# embededwebcam.net
KiCad netlist of a schematic drawn in EAGLE
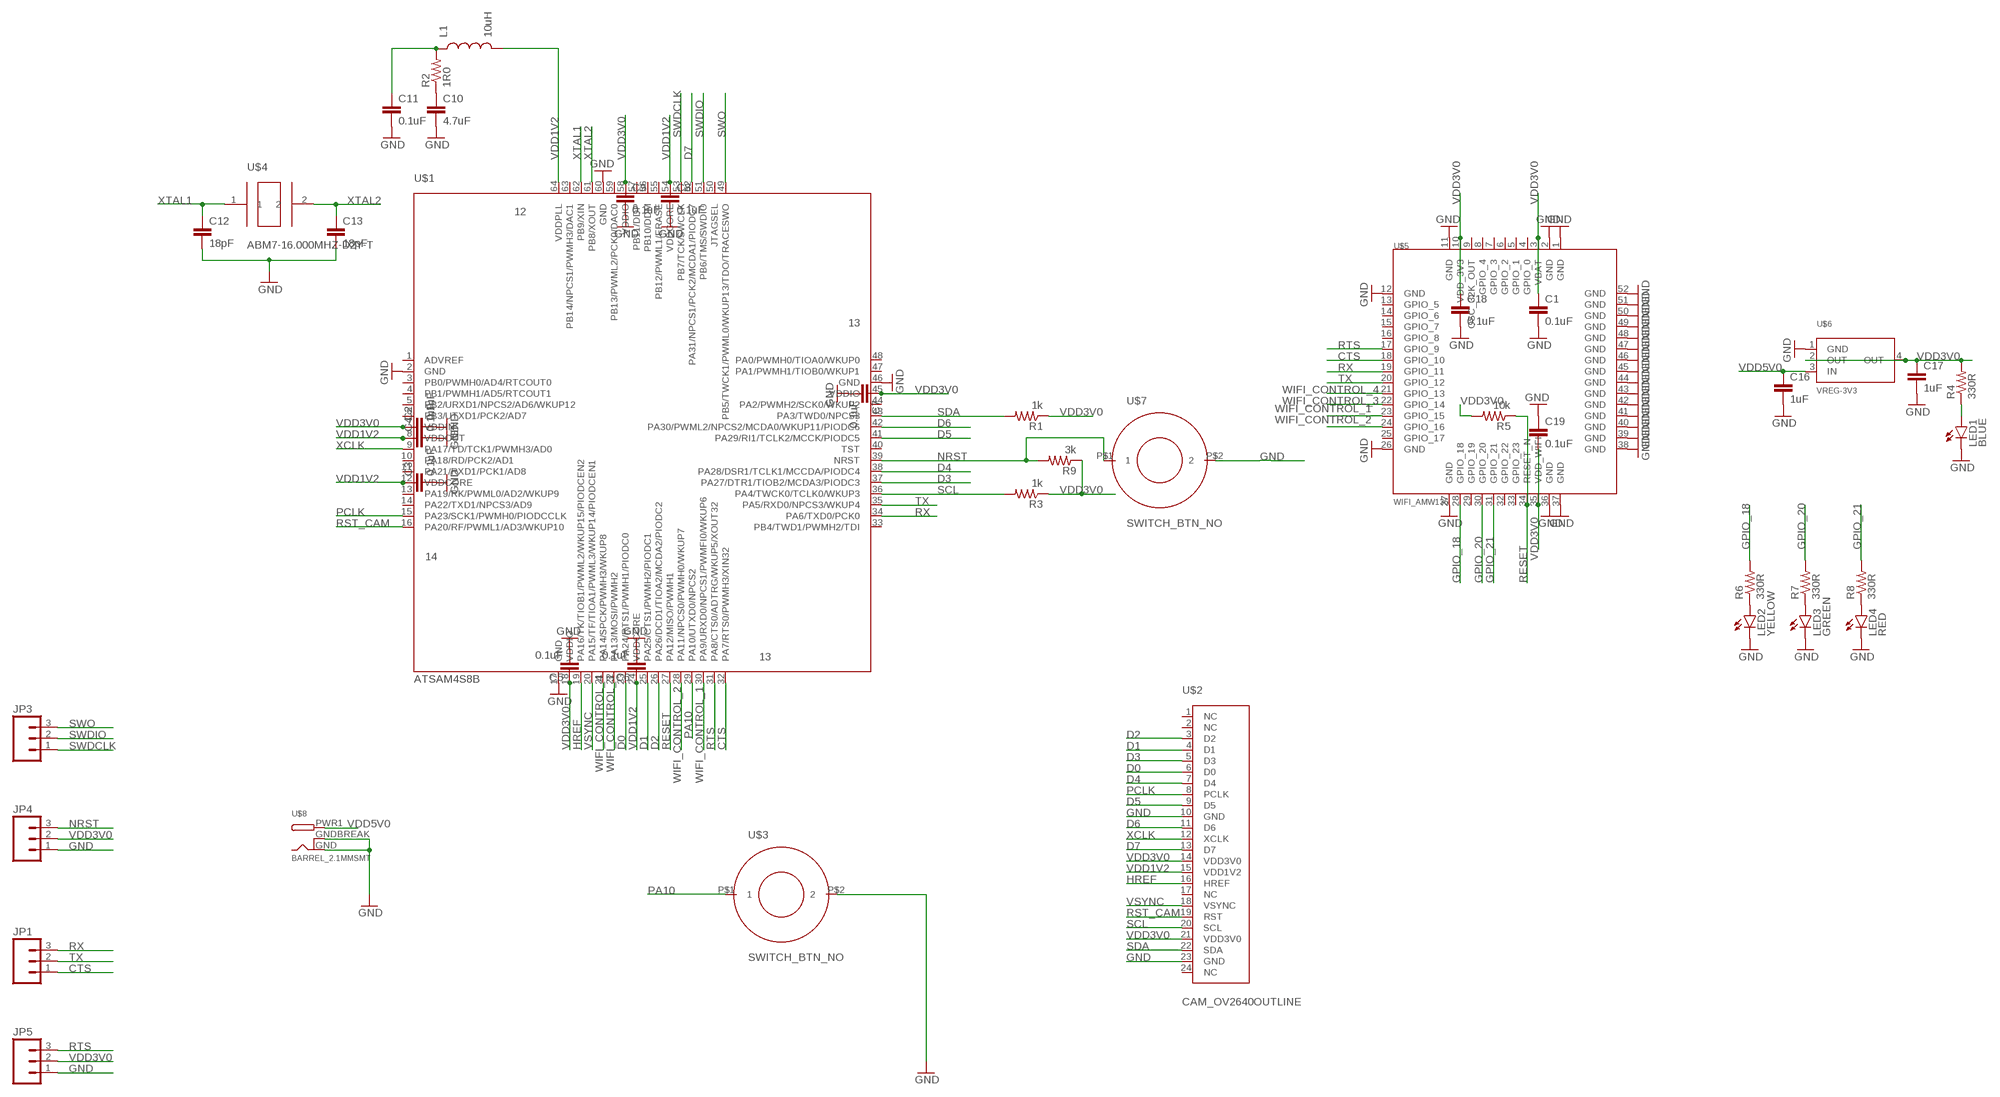
[diagram p0: schematic, sheet 1]

(export (version "E")
  (design (tool "Eeschema 10.0.6"))
  (components
    (comp (ref "C1")
      (value "0.1uF")
      (footprint "eagle-import:0805")
      (libsource (lib "eagle-import") (part "CAP"))
    )
    (comp (ref "C2")
      (value "0.1uF")
      (footprint "eagle-import:0805")
      (libsource (lib "eagle-import") (part "CAP0805"))
    )
    (comp (ref "C3")
      (value "0.1uF")
      (footprint "eagle-import:0805")
      (libsource (lib "eagle-import") (part "CAP0805"))
    )
    (comp (ref "C4")
      (value "0.1uF")
      (footprint "eagle-import:0805")
      (libsource (lib "eagle-import") (part "CAP0805"))
    )
    (comp (ref "C5")
      (value "0.1uF")
      (footprint "eagle-import:0805")
      (libsource (lib "eagle-import") (part "CAP0805"))
    )
    (comp (ref "C6")
      (value "0.1uF")
      (footprint "eagle-import:0805")
      (libsource (lib "eagle-import") (part "CAP0805"))
    )
    (comp (ref "C7")
      (value "0.1uF")
      (footprint "eagle-import:0805")
      (libsource (lib "eagle-import") (part "CAP0805"))
    )
    (comp (ref "C8")
      (value "0.1uF")
      (footprint "eagle-import:0805")
      (libsource (lib "eagle-import") (part "CAP0805"))
    )
    (comp (ref "C9")
      (value "0.1uF")
      (footprint "eagle-import:0805")
      (libsource (lib "eagle-import") (part "CAP0805"))
    )
    (comp (ref "C10")
      (value "4.7uF")
      (footprint "eagle-import:0805")
      (libsource (lib "eagle-import") (part "CAP0805"))
    )
    (comp (ref "C11")
      (value "0.1uF")
      (footprint "eagle-import:0805")
      (libsource (lib "eagle-import") (part "CAP0805"))
    )
    (comp (ref "C12")
      (value "18pF")
      (footprint "eagle-import:0805")
      (libsource (lib "eagle-import") (part "CAP0805"))
    )
    (comp (ref "C13")
      (value "18pF")
      (footprint "eagle-import:0805")
      (libsource (lib "eagle-import") (part "CAP0805"))
    )
    (comp (ref "C16")
      (value "1uF")
      (footprint "eagle-import:0805")
      (libsource (lib "eagle-import") (part "CAP"))
    )
    (comp (ref "C17")
      (value "1uF")
      (footprint "eagle-import:0805")
      (libsource (lib "eagle-import") (part "CAP"))
    )
    (comp (ref "C18")
      (value "0.1uF")
      (footprint "eagle-import:0805")
      (libsource (lib "eagle-import") (part "CAP"))
    )
    (comp (ref "C19")
      (value "0.1uF")
      (footprint "eagle-import:0805")
      (libsource (lib "eagle-import") (part "CAP"))
    )
    (comp (ref "JP1")
      (value "M03PTH")
      (footprint "eagle-import:1X03")
      (libsource (lib "eagle-import") (part "M03PTH"))
    )
    (comp (ref "JP3")
      (value "M03PTH")
      (footprint "eagle-import:1X03")
      (libsource (lib "eagle-import") (part "M03PTH"))
    )
    (comp (ref "JP4")
      (value "M03PTH")
      (footprint "eagle-import:1X03")
      (libsource (lib "eagle-import") (part "M03PTH"))
    )
    (comp (ref "JP5")
      (value "M03PTH")
      (footprint "eagle-import:1X03")
      (libsource (lib "eagle-import") (part "M03PTH"))
    )
    (comp (ref "L1")
      (value "10uH")
      (footprint "eagle-import:0805")
      (libsource (lib "eagle-import") (part "INDUCTOR0805"))
    )
    (comp (ref "LED1")
      (value "BLUE")
      (footprint "eagle-import:LED-0603")
      (libsource (lib "eagle-import") (part "LED0603"))
    )
    (comp (ref "LED2")
      (value "YELLOW")
      (footprint "eagle-import:LED-0603")
      (libsource (lib "eagle-import") (part "LED0603"))
    )
    (comp (ref "LED3")
      (value "GREEN")
      (footprint "eagle-import:LED-0603")
      (libsource (lib "eagle-import") (part "LED0603"))
    )
    (comp (ref "LED4")
      (value "RED")
      (footprint "eagle-import:LED-0603")
      (libsource (lib "eagle-import") (part "LED0603"))
    )
    (comp (ref "R1")
      (value "1k")
      (footprint "eagle-import:0805")
      (libsource (lib "eagle-import") (part "RESISTOR0805-RES"))
    )
    (comp (ref "R2")
      (value "1R0")
      (footprint "eagle-import:0805")
      (libsource (lib "eagle-import") (part "RESISTOR0805-RES"))
    )
    (comp (ref "R3")
      (value "1k")
      (footprint "eagle-import:0805")
      (libsource (lib "eagle-import") (part "RESISTOR0805-RES"))
    )
    (comp (ref "R4")
      (value "330R")
      (footprint "eagle-import:0805")
      (libsource (lib "eagle-import") (part "RES"))
    )
    (comp (ref "R5")
      (value "10k")
      (footprint "eagle-import:0805")
      (libsource (lib "eagle-import") (part "RES"))
    )
    (comp (ref "R6")
      (value "330R")
      (footprint "eagle-import:0805")
      (libsource (lib "eagle-import") (part "RES"))
    )
    (comp (ref "R7")
      (value "330R")
      (footprint "eagle-import:0805")
      (libsource (lib "eagle-import") (part "RES"))
    )
    (comp (ref "R8")
      (value "330R")
      (footprint "eagle-import:0805")
      (libsource (lib "eagle-import") (part "RES"))
    )
    (comp (ref "R9")
      (value "3k")
      (footprint "eagle-import:0805")
      (libsource (lib "eagle-import") (part "RESISTOR0805-RES"))
    )
    (comp (ref "U$1")
      (value "ATSAM4S8B")
      (footprint "eagle-import:QFP50P1200X1200X160-64N")
      (libsource (lib "eagle-import") (part "ATSAM4S8B"))
    )
    (comp (ref "U$2")
      (value "CAM_OV2640OUTLINE")
      (footprint "eagle-import:CAM_CONN")
      (libsource (lib "eagle-import") (part "CAM_OV2640OUTLINE"))
    )
    (comp (ref "U$3")
      (value "SWITCH_BTN_NO")
      (footprint "eagle-import:BTN_2")
      (libsource (lib "eagle-import") (part "SWITCH_BTN_NO"))
    )
    (comp (ref "U$4")
      (value "ABM7-16.000MHZ-D2Y-T")
      (footprint "eagle-import:ABM7-16.000MHZ-D2Y-T")
      (libsource (lib "eagle-import") (part "ABM7-16.000MHZ-D2Y-T"))
    )
    (comp (ref "U$5")
      (value "WIFI_AMW136")
      (footprint "eagle-import:AMW136")
      (libsource (lib "eagle-import") (part "WIFI_AMW136"))
    )
    (comp (ref "U$6")
      (value "VREG-3V3")
      (footprint "eagle-import:R-PDSO-G4_TI")
      (libsource (lib "eagle-import") (part "VREG-3V3"))
    )
    (comp (ref "U$7")
      (value "SWITCH_BTN_NO")
      (footprint "eagle-import:BTN_2")
      (libsource (lib "eagle-import") (part "SWITCH_BTN_NO"))
    )
    (comp (ref "U$8")
      (value "BARREL_2.1MMSMT")
      (footprint "eagle-import:DCJACK_2MM_SMT")
      (libsource (lib "eagle-import") (part "BARREL_2.1MMSMT"))
    )
  )
  (nets
    (net (code "1") (name "/CTS") (class "Default")
      (node (ref "JP1") (pin "1") (pinfunction "1_1") (pintype "passive"))
      (node (ref "U$1") (pin "32") (pinfunction "PA7/RTS0/PWMH3/XIN32_32") (pintype "bidirectional"))
      (node (ref "U$5") (pin "18") (pinfunction "GPIO_10_18") (pintype "bidirectional"))
    )
    (net (code "2") (name "/D0") (class "Default")
      (node (ref "U$1") (pin "23") (pinfunction "PA24/RTS1/PWMH1/PIODC0_23") (pintype "bidirectional"))
      (node (ref "U$2") (pin "6") (pinfunction "D0_6") (pintype "bidirectional"))
    )
    (net (code "3") (name "/D1") (class "Default")
      (node (ref "U$1") (pin "25") (pinfunction "PA25/CTS1/PWMH2/PIODC1_25") (pintype "bidirectional"))
      (node (ref "U$2") (pin "4") (pinfunction "D1_4") (pintype "bidirectional"))
    )
    (net (code "4") (name "/D2") (class "Default")
      (node (ref "U$1") (pin "26") (pinfunction "PA26/DCD1/TIOA2/MCDA2/PIODC2_26") (pintype "bidirectional"))
      (node (ref "U$2") (pin "3") (pinfunction "D2_3") (pintype "bidirectional"))
    )
    (net (code "5") (name "/D3") (class "Default")
      (node (ref "U$1") (pin "37") (pinfunction "PA27/DTR1/TIOB2/MCDA3/PIODC3_37") (pintype "bidirectional"))
      (node (ref "U$2") (pin "5") (pinfunction "D3_5") (pintype "bidirectional"))
    )
    (net (code "6") (name "/D4") (class "Default")
      (node (ref "U$1") (pin "38") (pinfunction "PA28/DSR1/TCLK1/MCCDA/PIODC4_38") (pintype "bidirectional"))
      (node (ref "U$2") (pin "7") (pinfunction "D4_7") (pintype "bidirectional"))
    )
    (net (code "7") (name "/D5") (class "Default")
      (node (ref "U$1") (pin "41") (pinfunction "PA29/RI1/TCLK2/MCCK/PIODC5_41") (pintype "bidirectional"))
      (node (ref "U$2") (pin "9") (pinfunction "D5_9") (pintype "bidirectional"))
    )
    (net (code "8") (name "/D6") (class "Default")
      (node (ref "U$1") (pin "42") (pinfunction "PA30/PWML2/NPCS2/MCDA0/WKUP11/PIODC6_42") (pintype "bidirectional"))
      (node (ref "U$2") (pin "11") (pinfunction "D6_11") (pintype "bidirectional"))
    )
    (net (code "9") (name "/D7") (class "Default")
      (node (ref "U$1") (pin "52") (pinfunction "PA31/NPCS1/PCK2/MCDA1/PIODC7_52") (pintype "bidirectional"))
      (node (ref "U$2") (pin "13") (pinfunction "D7_13") (pintype "bidirectional"))
    )
    (net (code "10") (name "/GPIO_18") (class "Default")
      (node (ref "R6") (pin "2") (pinfunction "2_2") (pintype "passive"))
      (node (ref "U$5") (pin "28") (pinfunction "GPIO_18_28") (pintype "bidirectional"))
    )
    (net (code "11") (name "/GPIO_20") (class "Default")
      (node (ref "R7") (pin "2") (pinfunction "2_2") (pintype "passive"))
      (node (ref "U$5") (pin "30") (pinfunction "GPIO_20_30") (pintype "bidirectional"))
    )
    (net (code "12") (name "/GPIO_21") (class "Default")
      (node (ref "R8") (pin "2") (pinfunction "2_2") (pintype "passive"))
      (node (ref "U$5") (pin "31") (pinfunction "GPIO_21_31") (pintype "bidirectional"))
    )
    (net (code "13") (name "/HREF") (class "Default")
      (node (ref "U$1") (pin "19") (pinfunction "PA16/TK/TIOB1/PWML2/WKUP15/PIODCEN2_19") (pintype "bidirectional"))
      (node (ref "U$2") (pin "16") (pinfunction "HREF_16") (pintype "bidirectional"))
    )
    (net (code "14") (name "/NRST") (class "Default")
      (node (ref "JP4") (pin "3") (pinfunction "3_3") (pintype "passive"))
      (node (ref "R9") (pin "2") (pinfunction "2_2") (pintype "passive"))
      (node (ref "U$1") (pin "39") (pinfunction "NRST_39") (pintype "bidirectional"))
      (node (ref "U$7") (pin "P$1") (pinfunction "1_P$1") (pintype "bidirectional"))
    )
    (net (code "15") (name "/PA10") (class "Default")
      (node (ref "U$1") (pin "29") (pinfunction "PA10/UTXD0/NPCS2_29") (pintype "bidirectional"))
      (node (ref "U$3") (pin "P$1") (pinfunction "1_P$1") (pintype "bidirectional"))
    )
    (net (code "16") (name "/PCLK") (class "Default")
      (node (ref "U$1") (pin "15") (pinfunction "PA23/SCK1/PWMH0/PIODCCLK_15") (pintype "bidirectional"))
      (node (ref "U$2") (pin "8") (pinfunction "PCLK_8") (pintype "bidirectional"))
    )
    (net (code "17") (name "/RESET") (class "Default")
      (node (ref "R5") (pin "1") (pinfunction "1_1") (pintype "passive"))
      (node (ref "U$1") (pin "27") (pinfunction "PA12/MISO/PWMH1_27") (pintype "bidirectional"))
      (node (ref "U$5") (pin "34") (pinfunction "RESET_N_34") (pintype "bidirectional"))
    )
    (net (code "18") (name "/RST_CAM") (class "Default")
      (node (ref "U$1") (pin "16") (pinfunction "PA20/RF/PWML1/AD3/WKUP10_16") (pintype "bidirectional"))
      (node (ref "U$2") (pin "19") (pinfunction "RST_19") (pintype "bidirectional"))
    )
    (net (code "19") (name "/RTS") (class "Default")
      (node (ref "JP5") (pin "3") (pinfunction "3_3") (pintype "passive"))
      (node (ref "U$1") (pin "31") (pinfunction "PA8/CTS0/ADTRG/WKUP5/XOUT32_31") (pintype "bidirectional"))
      (node (ref "U$5") (pin "17") (pinfunction "GPIO_9_17") (pintype "bidirectional"))
    )
    (net (code "20") (name "/RX") (class "Default")
      (node (ref "JP1") (pin "3") (pinfunction "3_3") (pintype "passive"))
      (node (ref "U$1") (pin "34") (pinfunction "PA6/TXD0/PCK0_34") (pintype "bidirectional"))
      (node (ref "U$5") (pin "19") (pinfunction "GPIO_11_19") (pintype "bidirectional"))
    )
    (net (code "21") (name "/SCL") (class "Default")
      (node (ref "R3") (pin "2") (pinfunction "2_2") (pintype "passive"))
      (node (ref "U$1") (pin "36") (pinfunction "PA4/TWCK0/TCLK0/WKUP3_36") (pintype "bidirectional"))
      (node (ref "U$2") (pin "20") (pinfunction "SCL_20") (pintype "bidirectional"))
    )
    (net (code "22") (name "/SDA") (class "Default")
      (node (ref "R1") (pin "2") (pinfunction "2_2") (pintype "passive"))
      (node (ref "U$1") (pin "43") (pinfunction "PA3/TWD0/NPCS3_43") (pintype "bidirectional"))
      (node (ref "U$2") (pin "22") (pinfunction "SDA_22") (pintype "bidirectional"))
    )
    (net (code "23") (name "/SWDCLK") (class "Default")
      (node (ref "JP3") (pin "1") (pinfunction "1_1") (pintype "passive"))
      (node (ref "U$1") (pin "53") (pinfunction "PB7/TCK/SWCLK_53") (pintype "bidirectional"))
    )
    (net (code "24") (name "/SWDIO") (class "Default")
      (node (ref "JP3") (pin "2") (pinfunction "2_2") (pintype "passive"))
      (node (ref "U$1") (pin "51") (pinfunction "PB6/TMS/SWDIO_51") (pintype "bidirectional"))
    )
    (net (code "25") (name "/SWO") (class "Default")
      (node (ref "JP3") (pin "3") (pinfunction "3_3") (pintype "passive"))
      (node (ref "U$1") (pin "49") (pinfunction "PB5/TWCK1/PWML0/WKUP13/TDO/TRACESWO_49") (pintype "bidirectional"))
    )
    (net (code "26") (name "/TX") (class "Default")
      (node (ref "JP1") (pin "2") (pinfunction "2_2") (pintype "passive"))
      (node (ref "U$1") (pin "35") (pinfunction "PA5/RXD0/NPCS3/WKUP4_35") (pintype "bidirectional"))
      (node (ref "U$5") (pin "20") (pinfunction "GPIO_12_20") (pintype "bidirectional"))
    )
    (net (code "27") (name "/VDD1V2") (class "Default")
      (node (ref "C3") (pin "1") (pinfunction "1_1") (pintype "passive"))
      (node (ref "C4") (pin "1") (pinfunction "1_1") (pintype "passive"))
      (node (ref "C6") (pin "1") (pinfunction "1_1") (pintype "passive"))
      (node (ref "C8") (pin "1") (pinfunction "1_1") (pintype "passive"))
      (node (ref "L1") (pin "2") (pinfunction "2_2") (pintype "passive"))
      (node (ref "U$1") (pin "12") (pinfunction "VDDCORE_12") (pintype "bidirectional"))
      (node (ref "U$1") (pin "24") (pinfunction "VDDCORE_24") (pintype "bidirectional"))
      (node (ref "U$1") (pin "54") (pinfunction "VDDCORE_54") (pintype "bidirectional"))
      (node (ref "U$1") (pin "64") (pinfunction "VDDPLL_64") (pintype "bidirectional"))
      (node (ref "U$1") (pin "8") (pinfunction "VDDOUT_8") (pintype "bidirectional"))
      (node (ref "U$2") (pin "15") (pinfunction "VDD1V2_15") (pintype "bidirectional"))
    )
    (net (code "28") (name "/VDD3V0") (class "Default")
      (node (ref "C1") (pin "1") (pinfunction "1_1") (pintype "passive"))
      (node (ref "C17") (pin "1") (pinfunction "1_1") (pintype "passive"))
      (node (ref "C18") (pin "1") (pinfunction "1_1") (pintype "passive"))
      (node (ref "C19") (pin "2") (pinfunction "2_2") (pintype "passive"))
      (node (ref "C2") (pin "1") (pinfunction "1_1") (pintype "passive"))
      (node (ref "C5") (pin "1") (pinfunction "1_1") (pintype "passive"))
      (node (ref "C7") (pin "1") (pinfunction "1_1") (pintype "passive"))
      (node (ref "C9") (pin "1") (pinfunction "1_1") (pintype "passive"))
      (node (ref "JP4") (pin "2") (pinfunction "2_2") (pintype "passive"))
      (node (ref "JP5") (pin "2") (pinfunction "2_2") (pintype "passive"))
      (node (ref "R1") (pin "1") (pinfunction "1_1") (pintype "passive"))
      (node (ref "R3") (pin "1") (pinfunction "1_1") (pintype "passive"))
      (node (ref "R4") (pin "2") (pinfunction "2_2") (pintype "passive"))
      (node (ref "R5") (pin "2") (pinfunction "2_2") (pintype "passive"))
      (node (ref "R9") (pin "1") (pinfunction "1_1") (pintype "passive"))
      (node (ref "U$1") (pin "18") (pinfunction "VDDIO_18") (pintype "bidirectional"))
      (node (ref "U$1") (pin "45") (pinfunction "VDDIO_45") (pintype "bidirectional"))
      (node (ref "U$1") (pin "58") (pinfunction "VDDIO_58") (pintype "bidirectional"))
      (node (ref "U$1") (pin "7") (pinfunction "VDDIN_7") (pintype "bidirectional"))
      (node (ref "U$2") (pin "14") (pinfunction "VDD3V0_14") (pintype "bidirectional"))
      (node (ref "U$2") (pin "21") (pinfunction "VDD3V0_21") (pintype "bidirectional"))
      (node (ref "U$5") (pin "10") (pinfunction "VDD_3V3_10") (pintype "bidirectional"))
      (node (ref "U$5") (pin "3") (pinfunction "VBAT_3") (pintype "bidirectional"))
      (node (ref "U$5") (pin "35") (pinfunction "VDD_WIFI_35") (pintype "bidirectional"))
      (node (ref "U$6") (pin "2") (pinfunction "OUT_2") (pintype "bidirectional"))
      (node (ref "U$6") (pin "4") (pinfunction "OUT_4") (pintype "bidirectional"))
    )
    (net (code "29") (name "/VDD5V0") (class "Default")
      (node (ref "C16") (pin "1") (pinfunction "1_1") (pintype "passive"))
      (node (ref "U$6") (pin "3") (pinfunction "IN_3") (pintype "bidirectional"))
      (node (ref "U$8") (pin "PWR1") (pinfunction "PWR_PWR1") (pintype "power_in"))
    )
    (net (code "30") (name "/VSYNC") (class "Default")
      (node (ref "U$1") (pin "20") (pinfunction "PA15/TF/TIOA1/PWML3/WKUP14/PIODCEN1_20") (pintype "bidirectional"))
      (node (ref "U$2") (pin "18") (pinfunction "VSYNC_18") (pintype "bidirectional"))
    )
    (net (code "31") (name "/WIFI_CONTROL_1") (class "Default")
      (node (ref "U$1") (pin "30") (pinfunction "PA9/URXD0/NPCS1/PWMFI0/WKUP6_30") (pintype "bidirectional"))
      (node (ref "U$5") (pin "24") (pinfunction "GPIO_16_24") (pintype "bidirectional"))
    )
    (net (code "32") (name "/WIFI_CONTROL_2") (class "Default")
      (node (ref "U$1") (pin "28") (pinfunction "PA11/NPCS0/PWMH0/WKUP7_28") (pintype "bidirectional"))
      (node (ref "U$5") (pin "23") (pinfunction "GPIO_15_23") (pintype "bidirectional"))
    )
    (net (code "33") (name "/WIFI_CONTROL_3") (class "Default")
      (node (ref "U$1") (pin "22") (pinfunction "PA13/MOSI/PWMH2_22") (pintype "bidirectional"))
      (node (ref "U$5") (pin "22") (pinfunction "GPIO_14_22") (pintype "bidirectional"))
    )
    (net (code "34") (name "/WIFI_CONTROL_4") (class "Default")
      (node (ref "U$1") (pin "21") (pinfunction "PA14/SPCK/PWMH3/WKUP8_21") (pintype "bidirectional"))
      (node (ref "U$5") (pin "21") (pinfunction "GPIO_13_21") (pintype "bidirectional"))
    )
    (net (code "35") (name "/XCLK") (class "Default")
      (node (ref "U$1") (pin "9") (pinfunction "PA17/TD/TCK1/PWMH3/AD0_9") (pintype "bidirectional"))
      (node (ref "U$2") (pin "12") (pinfunction "XCLK_12") (pintype "bidirectional"))
    )
    (net (code "36") (name "/XTAL1") (class "Default")
      (node (ref "C12") (pin "1") (pinfunction "1_1") (pintype "passive"))
      (node (ref "U$1") (pin "62") (pinfunction "PB9/XIN_62") (pintype "bidirectional"))
      (node (ref "U$4") (pin "1") (pinfunction "1_1") (pintype "bidirectional"))
    )
    (net (code "37") (name "/XTAL2") (class "Default")
      (node (ref "C13") (pin "1") (pinfunction "1_1") (pintype "passive"))
      (node (ref "U$1") (pin "61") (pinfunction "PB8/XOUT_61") (pintype "bidirectional"))
      (node (ref "U$4") (pin "2") (pinfunction "2_2") (pintype "bidirectional"))
    )
    (net (code "38") (name "GND") (class "Default")
      (node (ref "C1") (pin "2") (pinfunction "2_2") (pintype "passive"))
      (node (ref "C10") (pin "2") (pinfunction "2_2") (pintype "passive"))
      (node (ref "C11") (pin "2") (pinfunction "2_2") (pintype "passive"))
      (node (ref "C12") (pin "2") (pinfunction "2_2") (pintype "passive"))
      (node (ref "C13") (pin "2") (pinfunction "2_2") (pintype "passive"))
      (node (ref "C16") (pin "2") (pinfunction "2_2") (pintype "passive"))
      (node (ref "C17") (pin "2") (pinfunction "2_2") (pintype "passive"))
      (node (ref "C18") (pin "2") (pinfunction "2_2") (pintype "passive"))
      (node (ref "C19") (pin "1") (pinfunction "1_1") (pintype "passive"))
      (node (ref "C2") (pin "2") (pinfunction "2_2") (pintype "passive"))
      (node (ref "C3") (pin "2") (pinfunction "2_2") (pintype "passive"))
      (node (ref "C4") (pin "2") (pinfunction "2_2") (pintype "passive"))
      (node (ref "C5") (pin "2") (pinfunction "2_2") (pintype "passive"))
      (node (ref "C6") (pin "2") (pinfunction "2_2") (pintype "passive"))
      (node (ref "C7") (pin "2") (pinfunction "2_2") (pintype "passive"))
      (node (ref "C8") (pin "2") (pinfunction "2_2") (pintype "passive"))
      (node (ref "C9") (pin "2") (pinfunction "2_2") (pintype "passive"))
      (node (ref "JP4") (pin "1") (pinfunction "1_1") (pintype "passive"))
      (node (ref "JP5") (pin "1") (pinfunction "1_1") (pintype "passive"))
      (node (ref "LED1") (pin "C") (pinfunction "C_C") (pintype "passive"))
      (node (ref "LED2") (pin "C") (pinfunction "C_C") (pintype "passive"))
      (node (ref "LED3") (pin "C") (pinfunction "C_C") (pintype "passive"))
      (node (ref "LED4") (pin "C") (pinfunction "C_C") (pintype "passive"))
      (node (ref "U$1") (pin "17") (pinfunction "GND_17") (pintype "bidirectional"))
      (node (ref "U$1") (pin "2") (pinfunction "GND_2") (pintype "bidirectional"))
      (node (ref "U$1") (pin "46") (pinfunction "GND_46") (pintype "bidirectional"))
      (node (ref "U$1") (pin "60") (pinfunction "GND_60") (pintype "bidirectional"))
      (node (ref "U$2") (pin "10") (pinfunction "GND_10") (pintype "bidirectional"))
      (node (ref "U$2") (pin "23") (pinfunction "GND_23") (pintype "bidirectional"))
      (node (ref "U$3") (pin "P$2") (pinfunction "2_P$2") (pintype "bidirectional"))
      (node (ref "U$5") (pin "1") (pinfunction "GND_1") (pintype "bidirectional"))
      (node (ref "U$5") (pin "11") (pinfunction "GND_11") (pintype "bidirectional"))
      (node (ref "U$5") (pin "12") (pinfunction "GND_12") (pintype "bidirectional"))
      (node (ref "U$5") (pin "2") (pinfunction "GND_2") (pintype "bidirectional"))
      (node (ref "U$5") (pin "26") (pinfunction "GND_26") (pintype "bidirectional"))
      (node (ref "U$5") (pin "27") (pinfunction "GND_27") (pintype "bidirectional"))
      (node (ref "U$5") (pin "36") (pinfunction "GND_36") (pintype "bidirectional"))
      (node (ref "U$5") (pin "37") (pinfunction "GND_37") (pintype "bidirectional"))
      (node (ref "U$5") (pin "38") (pinfunction "GND_38") (pintype "bidirectional"))
      (node (ref "U$5") (pin "39") (pinfunction "GND_39") (pintype "bidirectional"))
      (node (ref "U$5") (pin "40") (pinfunction "GND_40") (pintype "bidirectional"))
      (node (ref "U$5") (pin "41") (pinfunction "GND_41") (pintype "bidirectional"))
      (node (ref "U$5") (pin "42") (pinfunction "GND_42") (pintype "bidirectional"))
      (node (ref "U$5") (pin "43") (pinfunction "GND_43") (pintype "bidirectional"))
      (node (ref "U$5") (pin "44") (pinfunction "GND_44") (pintype "bidirectional"))
      (node (ref "U$5") (pin "45") (pinfunction "GND_45") (pintype "bidirectional"))
      (node (ref "U$5") (pin "46") (pinfunction "GND_46") (pintype "bidirectional"))
      (node (ref "U$5") (pin "47") (pinfunction "GND_47") (pintype "bidirectional"))
      (node (ref "U$5") (pin "48") (pinfunction "GND_48") (pintype "bidirectional"))
      (node (ref "U$5") (pin "49") (pinfunction "GND_49") (pintype "bidirectional"))
      (node (ref "U$5") (pin "50") (pinfunction "GND_50") (pintype "bidirectional"))
      (node (ref "U$5") (pin "51") (pinfunction "GND_51") (pintype "bidirectional"))
      (node (ref "U$5") (pin "52") (pinfunction "GND_52") (pintype "bidirectional"))
      (node (ref "U$6") (pin "1") (pinfunction "GND_1") (pintype "bidirectional"))
      (node (ref "U$7") (pin "P$2") (pinfunction "2_P$2") (pintype "bidirectional"))
      (node (ref "U$8") (pin "GND") (pinfunction "GND_GND") (pintype "power_in"))
      (node (ref "U$8") (pin "GNDBREAK") (pinfunction "GNDBREAK_GNDBREAK") (pintype "power_in"))
    )
    (net (code "39") (name "Net-(C10-Pad1)") (class "Default")
      (node (ref "C10") (pin "1") (pinfunction "1_1") (pintype "passive"))
      (node (ref "R2") (pin "1") (pinfunction "1_1") (pintype "passive"))
    )
    (net (code "40") (name "Net-(C11-Pad1)") (class "Default")
      (node (ref "C11") (pin "1") (pinfunction "1_1") (pintype "passive"))
      (node (ref "L1") (pin "1") (pinfunction "1_1") (pintype "passive"))
      (node (ref "R2") (pin "2") (pinfunction "2_2") (pintype "passive"))
    )
    (net (code "41") (name "Net-(LED1-PadA)") (class "Default")
      (node (ref "LED1") (pin "A") (pinfunction "A_A") (pintype "passive"))
      (node (ref "R4") (pin "1") (pinfunction "1_1") (pintype "passive"))
    )
    (net (code "42") (name "Net-(LED2-PadA)") (class "Default")
      (node (ref "LED2") (pin "A") (pinfunction "A_A") (pintype "passive"))
      (node (ref "R6") (pin "1") (pinfunction "1_1") (pintype "passive"))
    )
    (net (code "43") (name "Net-(LED3-PadA)") (class "Default")
      (node (ref "LED3") (pin "A") (pinfunction "A_A") (pintype "passive"))
      (node (ref "R7") (pin "1") (pinfunction "1_1") (pintype "passive"))
    )
    (net (code "44") (name "Net-(LED4-PadA)") (class "Default")
      (node (ref "LED4") (pin "A") (pinfunction "A_A") (pintype "passive"))
      (node (ref "R8") (pin "1") (pinfunction "1_1") (pintype "passive"))
    )
    (net (code "45") (name "unconnected-(U$1-ADVREF-Pad1)") (class "Default")
      (node (ref "U$1") (pin "1") (pinfunction "ADVREF_1") (pintype "bidirectional"))
    )
    (net (code "46") (name "unconnected-(U$1-JTAGSEL-Pad50)") (class "Default")
      (node (ref "U$1") (pin "50") (pinfunction "JTAGSEL_50") (pintype "bidirectional"))
    )
    (net (code "47") (name "unconnected-(U$1-PA0{slash}PWMH0{slash}TIOA0{slash}WKUP0-Pad48)") (class "Default")
      (node (ref "U$1") (pin "48") (pinfunction "PA0/PWMH0/TIOA0/WKUP0_48") (pintype "bidirectional"))
    )
    (net (code "48") (name "unconnected-(U$1-PA1{slash}PWMH1{slash}TIOB0{slash}WKUP1-Pad47)") (class "Default")
      (node (ref "U$1") (pin "47") (pinfunction "PA1/PWMH1/TIOB0/WKUP1_47") (pintype "bidirectional"))
    )
    (net (code "49") (name "unconnected-(U$1-PA2{slash}PWMH2{slash}SCK0{slash}WKUP2-Pad44)") (class "Default")
      (node (ref "U$1") (pin "44") (pinfunction "PA2/PWMH2/SCK0/WKUP2_44") (pintype "bidirectional"))
    )
    (net (code "50") (name "unconnected-(U$1-PA18{slash}RD{slash}PCK2{slash}AD1-Pad10)") (class "Default")
      (node (ref "U$1") (pin "10") (pinfunction "PA18/RD/PCK2/AD1_10") (pintype "bidirectional"))
    )
    (net (code "51") (name "unconnected-(U$1-PA19{slash}RK{slash}PWML0{slash}AD2{slash}WKUP9-Pad13)") (class "Default")
      (node (ref "U$1") (pin "13") (pinfunction "PA19/RK/PWML0/AD2/WKUP9_13") (pintype "bidirectional"))
    )
    (net (code "52") (name "unconnected-(U$1-PA21{slash}RXD1{slash}PCK1{slash}AD8-Pad11)") (class "Default")
      (node (ref "U$1") (pin "11") (pinfunction "PA21/RXD1/PCK1/AD8_11") (pintype "bidirectional"))
    )
    (net (code "53") (name "unconnected-(U$1-PA22{slash}TXD1{slash}NPCS3{slash}AD9-Pad14)") (class "Default")
      (node (ref "U$1") (pin "14") (pinfunction "PA22/TXD1/NPCS3/AD9_14") (pintype "bidirectional"))
    )
    (net (code "54") (name "unconnected-(U$1-PB0{slash}PWMH0{slash}AD4{slash}RTCOUT0-Pad3)") (class "Default")
      (node (ref "U$1") (pin "3") (pinfunction "PB0/PWMH0/AD4/RTCOUT0_3") (pintype "bidirectional"))
    )
    (net (code "55") (name "unconnected-(U$1-PB1{slash}PWMH1{slash}AD5{slash}RTCOUT1-Pad4)") (class "Default")
      (node (ref "U$1") (pin "4") (pinfunction "PB1/PWMH1/AD5/RTCOUT1_4") (pintype "bidirectional"))
    )
    (net (code "56") (name "unconnected-(U$1-PB2{slash}URXD1{slash}NPCS2{slash}AD6{slash}WKUP12-Pad5)") (class "Default")
      (node (ref "U$1") (pin "5") (pinfunction "PB2/URXD1/NPCS2/AD6/WKUP12_5") (pintype "bidirectional"))
    )
    (net (code "57") (name "unconnected-(U$1-PB3{slash}UTXD1{slash}PCK2{slash}AD7-Pad6)") (class "Default")
      (node (ref "U$1") (pin "6") (pinfunction "PB3/UTXD1/PCK2/AD7_6") (pintype "bidirectional"))
    )
    (net (code "58") (name "unconnected-(U$1-PB4{slash}TWD1{slash}PWMH2{slash}TDI-Pad33)") (class "Default")
      (node (ref "U$1") (pin "33") (pinfunction "PB4/TWD1/PWMH2/TDI_33") (pintype "bidirectional"))
    )
    (net (code "59") (name "unconnected-(U$1-PB10{slash}DDM-Pad56)") (class "Default")
      (node (ref "U$1") (pin "56") (pinfunction "PB10/DDM_56") (pintype "bidirectional"))
    )
    (net (code "60") (name "unconnected-(U$1-PB11{slash}DDP-Pad57)") (class "Default")
      (node (ref "U$1") (pin "57") (pinfunction "PB11/DDP_57") (pintype "bidirectional"))
    )
    (net (code "61") (name "unconnected-(U$1-PB12{slash}PWML1{slash}ERASE-Pad55)") (class "Default")
      (node (ref "U$1") (pin "55") (pinfunction "PB12/PWML1/ERASE_55") (pintype "bidirectional"))
    )
    (net (code "62") (name "unconnected-(U$1-PB13{slash}PWML2{slash}PCK0{slash}DAC0-Pad59)") (class "Default")
      (node (ref "U$1") (pin "59") (pinfunction "PB13/PWML2/PCK0/DAC0_59") (pintype "bidirectional"))
    )
    (net (code "63") (name "unconnected-(U$1-PB14{slash}NPCS1{slash}PWMH3{slash}DAC1-Pad63)") (class "Default")
      (node (ref "U$1") (pin "63") (pinfunction "PB14/NPCS1/PWMH3/DAC1_63") (pintype "bidirectional"))
    )
    (net (code "64") (name "unconnected-(U$1-TST-Pad40)") (class "Default")
      (node (ref "U$1") (pin "40") (pinfunction "TST_40") (pintype "bidirectional"))
    )
    (net (code "65") (name "unconnected-(U$2-NC-Pad1)") (class "Default")
      (node (ref "U$2") (pin "1") (pinfunction "NC_1") (pintype "bidirectional"))
    )
    (net (code "66") (name "unconnected-(U$2-NC-Pad2)") (class "Default")
      (node (ref "U$2") (pin "2") (pinfunction "NC_2") (pintype "bidirectional"))
    )
    (net (code "67") (name "unconnected-(U$2-NC-Pad17)") (class "Default")
      (node (ref "U$2") (pin "17") (pinfunction "NC_17") (pintype "bidirectional"))
    )
    (net (code "68") (name "unconnected-(U$2-NC-Pad24)") (class "Default")
      (node (ref "U$2") (pin "24") (pinfunction "NC_24") (pintype "bidirectional"))
    )
    (net (code "69") (name "unconnected-(U$5-GPIO_0-Pad4)") (class "Default")
      (node (ref "U$5") (pin "4") (pinfunction "GPIO_0_4") (pintype "bidirectional"))
    )
    (net (code "70") (name "unconnected-(U$5-GPIO_1-Pad5)") (class "Default")
      (node (ref "U$5") (pin "5") (pinfunction "GPIO_1_5") (pintype "bidirectional"))
    )
    (net (code "71") (name "unconnected-(U$5-GPIO_2-Pad6)") (class "Default")
      (node (ref "U$5") (pin "6") (pinfunction "GPIO_2_6") (pintype "bidirectional"))
    )
    (net (code "72") (name "unconnected-(U$5-GPIO_3-Pad7)") (class "Default")
      (node (ref "U$5") (pin "7") (pinfunction "GPIO_3_7") (pintype "bidirectional"))
    )
    (net (code "73") (name "unconnected-(U$5-GPIO_4-Pad8)") (class "Default")
      (node (ref "U$5") (pin "8") (pinfunction "GPIO_4_8") (pintype "bidirectional"))
    )
    (net (code "74") (name "unconnected-(U$5-GPIO_5-Pad13)") (class "Default")
      (node (ref "U$5") (pin "13") (pinfunction "GPIO_5_13") (pintype "bidirectional"))
    )
    (net (code "75") (name "unconnected-(U$5-GPIO_6-Pad14)") (class "Default")
      (node (ref "U$5") (pin "14") (pinfunction "GPIO_6_14") (pintype "bidirectional"))
    )
    (net (code "76") (name "unconnected-(U$5-GPIO_7-Pad15)") (class "Default")
      (node (ref "U$5") (pin "15") (pinfunction "GPIO_7_15") (pintype "bidirectional"))
    )
    (net (code "77") (name "unconnected-(U$5-GPIO_8-Pad16)") (class "Default")
      (node (ref "U$5") (pin "16") (pinfunction "GPIO_8_16") (pintype "bidirectional"))
    )
    (net (code "78") (name "unconnected-(U$5-GPIO_17-Pad25)") (class "Default")
      (node (ref "U$5") (pin "25") (pinfunction "GPIO_17_25") (pintype "bidirectional"))
    )
    (net (code "79") (name "unconnected-(U$5-GPIO_19-Pad29)") (class "Default")
      (node (ref "U$5") (pin "29") (pinfunction "GPIO_19_29") (pintype "bidirectional"))
    )
    (net (code "80") (name "unconnected-(U$5-GPIO_22-Pad32)") (class "Default")
      (node (ref "U$5") (pin "32") (pinfunction "GPIO_22_32") (pintype "bidirectional"))
    )
    (net (code "81") (name "unconnected-(U$5-GPIO_23-Pad33)") (class "Default")
      (node (ref "U$5") (pin "33") (pinfunction "GPIO_23_33") (pintype "bidirectional"))
    )
    (net (code "82") (name "unconnected-(U$5-OSC_32K_OUT-Pad9)") (class "Default")
      (node (ref "U$5") (pin "9") (pinfunction "OSC_32K_OUT_9") (pintype "bidirectional"))
    )
  )
)
